# Shield.net
KiCad netlist of a schematic drawn in EAGLE
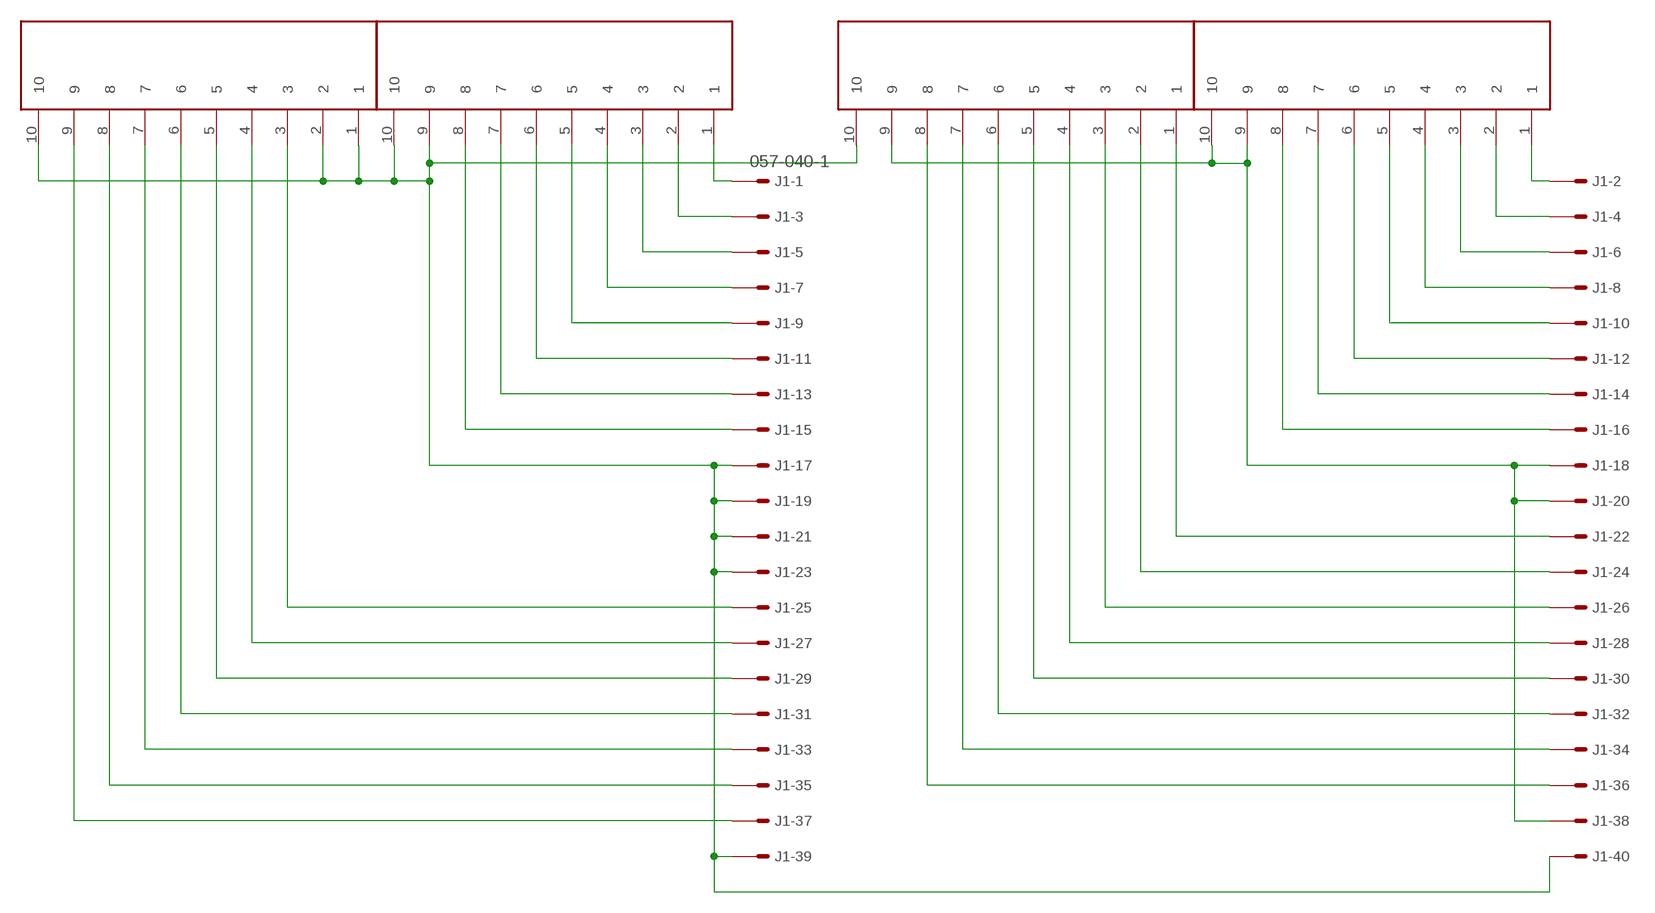
[diagram p0: schematic, sheet 1]

(export (version "E")
  (design (tool "Eeschema 10.0.6"))
  (components
    (comp (ref "J1")
      (value "057-040-1")
      (footprint "eagle-import:057-040-1")
      (fields (field (name "PARTNO") "SBH11-PBPC-D20-ST-BK"))
      (libsource (lib "eagle-import") (part "057-040-1"))
    )
    (comp (ref "TB1")
      (value "282847-10")
      (footprint "eagle-import:282847-10")
      (fields (field (name "PARTNO") "1-282847-0"))
      (libsource (lib "eagle-import") (part "282847-10"))
    )
    (comp (ref "TB2")
      (value "282847-10")
      (footprint "eagle-import:282847-10")
      (fields (field (name "PARTNO") "1-282847-0"))
      (libsource (lib "eagle-import") (part "282847-10"))
    )
    (comp (ref "TB3")
      (value "282847-10")
      (footprint "eagle-import:282847-10")
      (fields (field (name "PARTNO") "1-282847-0"))
      (libsource (lib "eagle-import") (part "282847-10"))
    )
    (comp (ref "TB4")
      (value "282847-10")
      (footprint "eagle-import:282847-10")
      (fields (field (name "PARTNO") "1-282847-0"))
      (libsource (lib "eagle-import") (part "282847-10"))
    )
  )
  (nets
    (net (code "1") (name "Net-(J1A-S)") (class "Default")
      (node (ref "J1") (pin "1") (pinfunction "S_1") (pintype "passive"))
      (node (ref "TB2") (pin "1") (pinfunction "1_1") (pintype "bidirectional"))
    )
    (net (code "2") (name "Net-(J1AA-S)") (class "Default")
      (node (ref "J1") (pin "33") (pinfunction "S_33") (pintype "passive"))
      (node (ref "TB1") (pin "7") (pinfunction "7_7") (pintype "bidirectional"))
    )
    (net (code "3") (name "Net-(J1AB-S)") (class "Default")
      (node (ref "J1") (pin "34") (pinfunction "S_34") (pintype "passive"))
      (node (ref "TB3") (pin "7") (pinfunction "7_7") (pintype "bidirectional"))
    )
    (net (code "4") (name "Net-(J1AC-S)") (class "Default")
      (node (ref "J1") (pin "35") (pinfunction "S_35") (pintype "passive"))
      (node (ref "TB1") (pin "8") (pinfunction "8_8") (pintype "bidirectional"))
    )
    (net (code "5") (name "Net-(J1AD-S)") (class "Default")
      (node (ref "J1") (pin "36") (pinfunction "S_36") (pintype "passive"))
      (node (ref "TB3") (pin "8") (pinfunction "8_8") (pintype "bidirectional"))
    )
    (net (code "6") (name "Net-(J1AE-S)") (class "Default")
      (node (ref "J1") (pin "37") (pinfunction "S_37") (pintype "passive"))
      (node (ref "TB1") (pin "9") (pinfunction "9_9") (pintype "bidirectional"))
    )
    (net (code "7") (name "Net-(J1AF-S)") (class "Default")
      (node (ref "J1") (pin "18") (pinfunction "S_18") (pintype "passive"))
      (node (ref "J1") (pin "20") (pinfunction "S_20") (pintype "passive"))
      (node (ref "J1") (pin "38") (pinfunction "S_38") (pintype "passive"))
      (node (ref "TB3") (pin "9") (pinfunction "9_9") (pintype "bidirectional"))
      (node (ref "TB4") (pin "10") (pinfunction "10_10") (pintype "bidirectional"))
      (node (ref "TB4") (pin "9") (pinfunction "9_9") (pintype "bidirectional"))
    )
    (net (code "8") (name "Net-(J1AG-S)") (class "Default")
      (node (ref "J1") (pin "17") (pinfunction "S_17") (pintype "passive"))
      (node (ref "J1") (pin "19") (pinfunction "S_19") (pintype "passive"))
      (node (ref "J1") (pin "21") (pinfunction "S_21") (pintype "passive"))
      (node (ref "J1") (pin "23") (pinfunction "S_23") (pintype "passive"))
      (node (ref "J1") (pin "39") (pinfunction "S_39") (pintype "passive"))
      (node (ref "J1") (pin "40") (pinfunction "S_40") (pintype "passive"))
      (node (ref "TB1") (pin "1") (pinfunction "1_1") (pintype "bidirectional"))
      (node (ref "TB1") (pin "10") (pinfunction "10_10") (pintype "bidirectional"))
      (node (ref "TB1") (pin "2") (pinfunction "2_2") (pintype "bidirectional"))
      (node (ref "TB2") (pin "10") (pinfunction "10_10") (pintype "bidirectional"))
      (node (ref "TB2") (pin "9") (pinfunction "9_9") (pintype "bidirectional"))
      (node (ref "TB3") (pin "10") (pinfunction "10_10") (pintype "bidirectional"))
    )
    (net (code "9") (name "Net-(J1AH-S)") (class "Default")
      (node (ref "J1") (pin "4") (pinfunction "S_4") (pintype "passive"))
      (node (ref "TB4") (pin "2") (pinfunction "2_2") (pintype "bidirectional"))
    )
    (net (code "10") (name "Net-(J1AJ-S)") (class "Default")
      (node (ref "J1") (pin "5") (pinfunction "S_5") (pintype "passive"))
      (node (ref "TB2") (pin "3") (pinfunction "3_3") (pintype "bidirectional"))
    )
    (net (code "11") (name "Net-(J1AK-S)") (class "Default")
      (node (ref "J1") (pin "6") (pinfunction "S_6") (pintype "passive"))
      (node (ref "TB4") (pin "3") (pinfunction "3_3") (pintype "bidirectional"))
    )
    (net (code "12") (name "Net-(J1AL-S)") (class "Default")
      (node (ref "J1") (pin "7") (pinfunction "S_7") (pintype "passive"))
      (node (ref "TB2") (pin "4") (pinfunction "4_4") (pintype "bidirectional"))
    )
    (net (code "13") (name "Net-(J1AM-S)") (class "Default")
      (node (ref "J1") (pin "8") (pinfunction "S_8") (pintype "passive"))
      (node (ref "TB4") (pin "4") (pinfunction "4_4") (pintype "bidirectional"))
    )
    (net (code "14") (name "Net-(J1AN-S)") (class "Default")
      (node (ref "J1") (pin "9") (pinfunction "S_9") (pintype "passive"))
      (node (ref "TB2") (pin "5") (pinfunction "5_5") (pintype "bidirectional"))
    )
    (net (code "15") (name "Net-(J1B-S)") (class "Default")
      (node (ref "J1") (pin "10") (pinfunction "S_10") (pintype "passive"))
      (node (ref "TB4") (pin "5") (pinfunction "5_5") (pintype "bidirectional"))
    )
    (net (code "16") (name "Net-(J1C-S)") (class "Default")
      (node (ref "J1") (pin "11") (pinfunction "S_11") (pintype "passive"))
      (node (ref "TB2") (pin "6") (pinfunction "6_6") (pintype "bidirectional"))
    )
    (net (code "17") (name "Net-(J1D-S)") (class "Default")
      (node (ref "J1") (pin "12") (pinfunction "S_12") (pintype "passive"))
      (node (ref "TB4") (pin "6") (pinfunction "6_6") (pintype "bidirectional"))
    )
    (net (code "18") (name "Net-(J1E-S)") (class "Default")
      (node (ref "J1") (pin "13") (pinfunction "S_13") (pintype "passive"))
      (node (ref "TB2") (pin "7") (pinfunction "7_7") (pintype "bidirectional"))
    )
    (net (code "19") (name "Net-(J1F-S)") (class "Default")
      (node (ref "J1") (pin "14") (pinfunction "S_14") (pintype "passive"))
      (node (ref "TB4") (pin "7") (pinfunction "7_7") (pintype "bidirectional"))
    )
    (net (code "20") (name "Net-(J1G-S)") (class "Default")
      (node (ref "J1") (pin "15") (pinfunction "S_15") (pintype "passive"))
      (node (ref "TB2") (pin "8") (pinfunction "8_8") (pintype "bidirectional"))
    )
    (net (code "21") (name "Net-(J1H-S)") (class "Default")
      (node (ref "J1") (pin "16") (pinfunction "S_16") (pintype "passive"))
      (node (ref "TB4") (pin "8") (pinfunction "8_8") (pintype "bidirectional"))
    )
    (net (code "22") (name "Net-(J1L-S)") (class "Default")
      (node (ref "J1") (pin "2") (pinfunction "S_2") (pintype "passive"))
      (node (ref "TB4") (pin "1") (pinfunction "1_1") (pintype "bidirectional"))
    )
    (net (code "23") (name "Net-(J1O-S)") (class "Default")
      (node (ref "J1") (pin "22") (pinfunction "S_22") (pintype "passive"))
      (node (ref "TB3") (pin "1") (pinfunction "1_1") (pintype "bidirectional"))
    )
    (net (code "24") (name "Net-(J1Q-S)") (class "Default")
      (node (ref "J1") (pin "24") (pinfunction "S_24") (pintype "passive"))
      (node (ref "TB3") (pin "2") (pinfunction "2_2") (pintype "bidirectional"))
    )
    (net (code "25") (name "Net-(J1R-S)") (class "Default")
      (node (ref "J1") (pin "25") (pinfunction "S_25") (pintype "passive"))
      (node (ref "TB1") (pin "3") (pinfunction "3_3") (pintype "bidirectional"))
    )
    (net (code "26") (name "Net-(J1S-S)") (class "Default")
      (node (ref "J1") (pin "26") (pinfunction "S_26") (pintype "passive"))
      (node (ref "TB3") (pin "3") (pinfunction "3_3") (pintype "bidirectional"))
    )
    (net (code "27") (name "Net-(J1T-S)") (class "Default")
      (node (ref "J1") (pin "27") (pinfunction "S_27") (pintype "passive"))
      (node (ref "TB1") (pin "4") (pinfunction "4_4") (pintype "bidirectional"))
    )
    (net (code "28") (name "Net-(J1U-S)") (class "Default")
      (node (ref "J1") (pin "28") (pinfunction "S_28") (pintype "passive"))
      (node (ref "TB3") (pin "4") (pinfunction "4_4") (pintype "bidirectional"))
    )
    (net (code "29") (name "Net-(J1V-S)") (class "Default")
      (node (ref "J1") (pin "29") (pinfunction "S_29") (pintype "passive"))
      (node (ref "TB1") (pin "5") (pinfunction "5_5") (pintype "bidirectional"))
    )
    (net (code "30") (name "Net-(J1W-S)") (class "Default")
      (node (ref "J1") (pin "3") (pinfunction "S_3") (pintype "passive"))
      (node (ref "TB2") (pin "2") (pinfunction "2_2") (pintype "bidirectional"))
    )
    (net (code "31") (name "Net-(J1X-S)") (class "Default")
      (node (ref "J1") (pin "30") (pinfunction "S_30") (pintype "passive"))
      (node (ref "TB3") (pin "5") (pinfunction "5_5") (pintype "bidirectional"))
    )
    (net (code "32") (name "Net-(J1Y-S)") (class "Default")
      (node (ref "J1") (pin "31") (pinfunction "S_31") (pintype "passive"))
      (node (ref "TB1") (pin "6") (pinfunction "6_6") (pintype "bidirectional"))
    )
    (net (code "33") (name "Net-(J1Z-S)") (class "Default")
      (node (ref "J1") (pin "32") (pinfunction "S_32") (pintype "passive"))
      (node (ref "TB3") (pin "6") (pinfunction "6_6") (pintype "bidirectional"))
    )
  )
)
